# expender.net
KiCad netlist of a schematic drawn in EAGLE
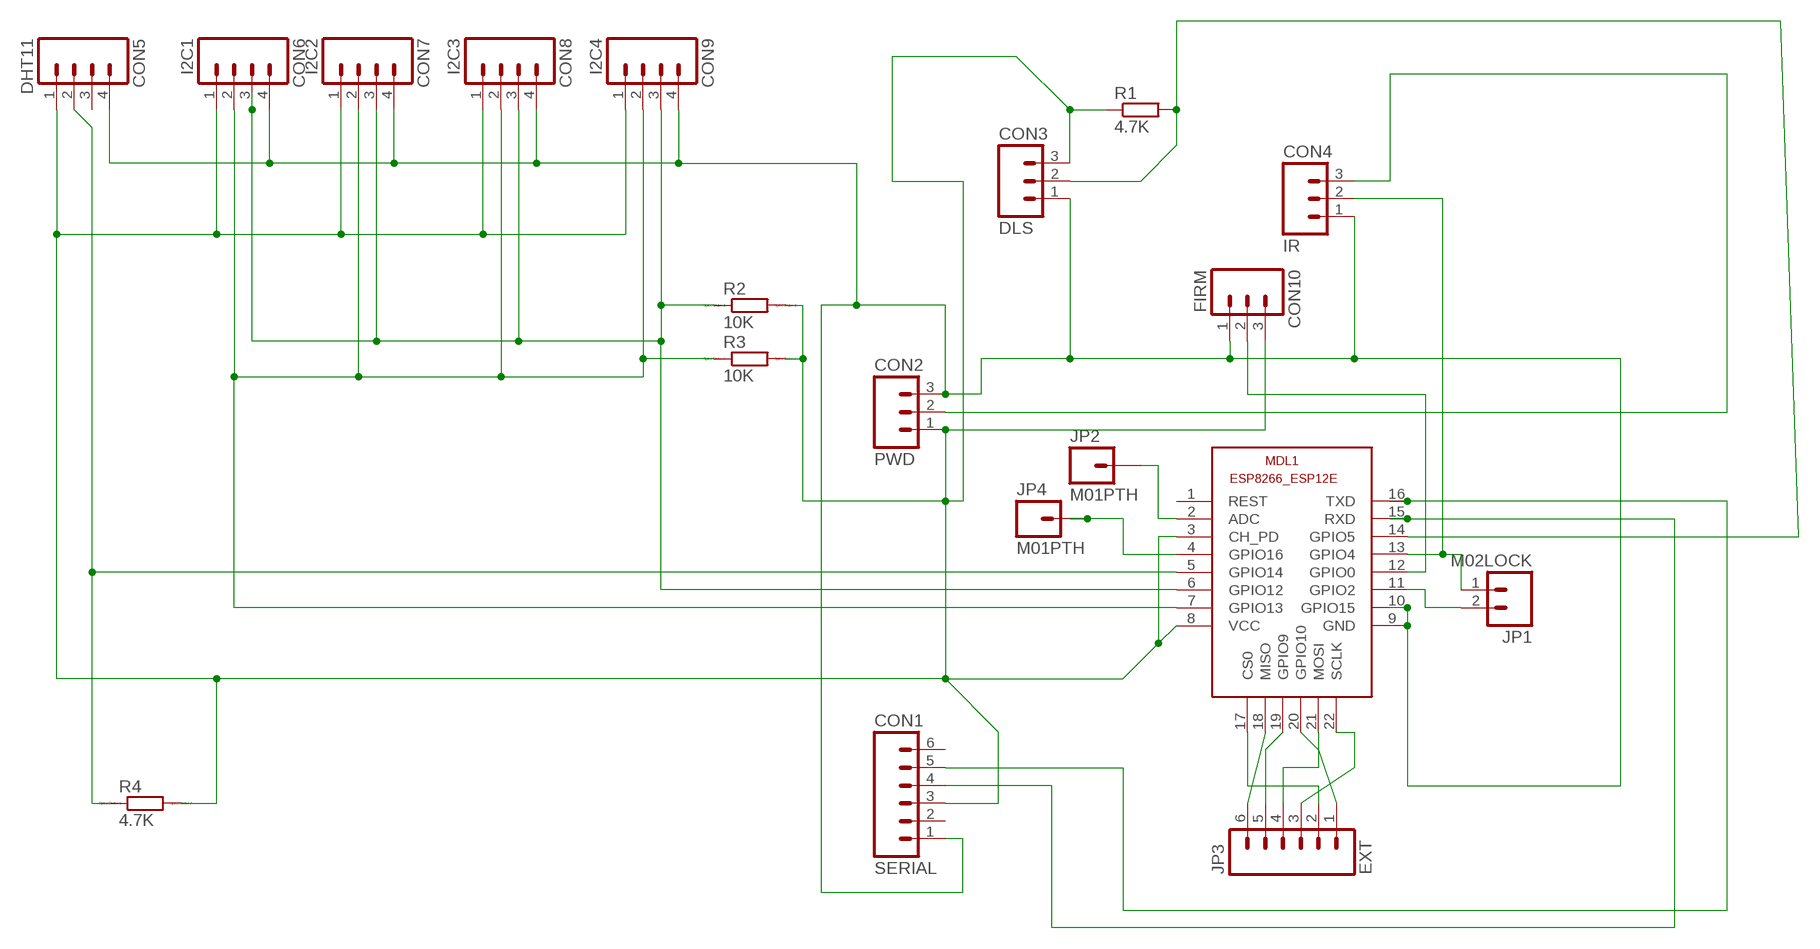
[diagram p0: schematic, sheet 1]

(export (version "E")
  (design (tool "Eeschema 10.0.6"))
  (components
    (comp (ref "CON1")
      (value "SERIAL")
      (footprint "eagle-import:1X06_LOCK")
      (libsource (lib "eagle-import") (part "M06LOCK"))
    )
    (comp (ref "CON2")
      (value "PWD")
      (footprint "eagle-import:1X03_LOCK")
      (libsource (lib "eagle-import") (part "M03LOCK"))
    )
    (comp (ref "CON3")
      (value "DLS")
      (footprint "eagle-import:1X03_LOCK")
      (libsource (lib "eagle-import") (part "M03LOCK"))
    )
    (comp (ref "CON4")
      (value "IR")
      (footprint "eagle-import:1X03_LOCK")
      (libsource (lib "eagle-import") (part "M03LOCK"))
    )
    (comp (ref "CON5")
      (value "DHT11")
      (footprint "eagle-import:1X04_LOCK")
      (libsource (lib "eagle-import") (part "M04LOCK"))
    )
    (comp (ref "CON6")
      (value "I2C1")
      (footprint "eagle-import:1X04_LOCK")
      (libsource (lib "eagle-import") (part "M04LOCK"))
    )
    (comp (ref "CON7")
      (value "I2C2")
      (footprint "eagle-import:1X04_LOCK")
      (libsource (lib "eagle-import") (part "M04LOCK"))
    )
    (comp (ref "CON8")
      (value "I2C3")
      (footprint "eagle-import:1X04_LOCK")
      (libsource (lib "eagle-import") (part "M04LOCK"))
    )
    (comp (ref "CON9")
      (value "I2C4")
      (footprint "eagle-import:1X04_LOCK")
      (libsource (lib "eagle-import") (part "M04LOCK"))
    )
    (comp (ref "CON10")
      (value "FIRM")
      (footprint "eagle-import:1X03_LOCK")
      (libsource (lib "eagle-import") (part "M03LOCK"))
    )
    (comp (ref "JP1")
      (value "M02LOCK")
      (footprint "eagle-import:1X02_LOCK")
      (libsource (lib "eagle-import") (part "M02LOCK"))
    )
    (comp (ref "JP2")
      (value "M01PTH")
      (footprint "eagle-import:1X01")
      (libsource (lib "eagle-import") (part "M01PTH"))
    )
    (comp (ref "JP3")
      (value "EXT")
      (footprint "eagle-import:1X06_LOCK")
      (libsource (lib "eagle-import") (part "M06LOCK"))
    )
    (comp (ref "JP4")
      (value "M01PTH")
      (footprint "eagle-import:1X01")
      (libsource (lib "eagle-import") (part "M01PTH"))
    )
    (comp (ref "MDL1")
      (value "ESP12E")
      (footprint "eagle-import:ESP8266-ESP12E")
      (libsource (lib "eagle-import") (part "ESP8266-12EESP8266-ESP12E"))
    )
    (comp (ref "R1")
      (value "4.7K")
      (footprint "eagle-import:0207_10")
      (libsource (lib "eagle-import") (part "R-EU_0207/10"))
    )
    (comp (ref "R2")
      (value "10K")
      (footprint "eagle-import:0207_10")
      (libsource (lib "eagle-import") (part "R0207/10"))
    )
    (comp (ref "R3")
      (value "10K")
      (footprint "eagle-import:0207_10")
      (libsource (lib "eagle-import") (part "R0207/10"))
    )
    (comp (ref "R4")
      (value "4.7K")
      (footprint "eagle-import:R1206")
      (libsource (lib "eagle-import") (part "RR1206"))
    )
  )
  (nets
    (net (code "1") (name "Net-(CON2-Pad2)") (class "Default")
      (node (ref "CON2") (pin "2") (pinfunction "2_2") (pintype "passive"))
      (node (ref "CON4") (pin "3") (pinfunction "3_3") (pintype "passive"))
    )
    (net (code "2") (name "Net-(MDL1-ADC)") (class "Default")
      (node (ref "JP2") (pin "1") (pinfunction "1_1") (pintype "passive"))
      (node (ref "MDL1") (pin "2") (pinfunction "ADC_2") (pintype "bidirectional"))
    )
    (net (code "3") (name "Net-(MDL1-CH_PD)") (class "Default")
      (node (ref "CON1") (pin "3") (pinfunction "3_3") (pintype "passive"))
      (node (ref "CON10") (pin "3") (pinfunction "3_3") (pintype "passive"))
      (node (ref "CON2") (pin "1") (pinfunction "1_1") (pintype "passive"))
      (node (ref "CON3") (pin "3") (pinfunction "3_3") (pintype "passive"))
      (node (ref "CON5") (pin "1") (pinfunction "1_1") (pintype "passive"))
      (node (ref "CON6") (pin "1") (pinfunction "1_1") (pintype "passive"))
      (node (ref "CON7") (pin "1") (pinfunction "1_1") (pintype "passive"))
      (node (ref "CON8") (pin "1") (pinfunction "1_1") (pintype "passive"))
      (node (ref "CON9") (pin "1") (pinfunction "1_1") (pintype "passive"))
      (node (ref "MDL1") (pin "3") (pinfunction "CH_PD_3") (pintype "bidirectional"))
      (node (ref "MDL1") (pin "8") (pinfunction "VCC_8") (pintype "bidirectional"))
      (node (ref "R1") (pin "1") (pinfunction "1_1") (pintype "passive"))
      (node (ref "R2") (pin "2") (pinfunction "2_2") (pintype "passive"))
      (node (ref "R3") (pin "2") (pinfunction "2_2") (pintype "passive"))
      (node (ref "R4") (pin "2") (pinfunction "2_2") (pintype "passive"))
    )
    (net (code "4") (name "Net-(MDL1-CS0)") (class "Default")
      (node (ref "JP3") (pin "2") (pinfunction "2_2") (pintype "passive"))
      (node (ref "MDL1") (pin "17") (pinfunction "CS0_17") (pintype "bidirectional"))
    )
    (net (code "5") (name "Net-(MDL1-GND)") (class "Default")
      (node (ref "CON1") (pin "1") (pinfunction "1_1") (pintype "passive"))
      (node (ref "CON10") (pin "1") (pinfunction "1_1") (pintype "passive"))
      (node (ref "CON2") (pin "3") (pinfunction "3_3") (pintype "passive"))
      (node (ref "CON3") (pin "1") (pinfunction "1_1") (pintype "passive"))
      (node (ref "CON4") (pin "1") (pinfunction "1_1") (pintype "passive"))
      (node (ref "CON5") (pin "4") (pinfunction "4_4") (pintype "passive"))
      (node (ref "CON6") (pin "4") (pinfunction "4_4") (pintype "passive"))
      (node (ref "CON7") (pin "4") (pinfunction "4_4") (pintype "passive"))
      (node (ref "CON8") (pin "4") (pinfunction "4_4") (pintype "passive"))
      (node (ref "CON9") (pin "4") (pinfunction "4_4") (pintype "passive"))
      (node (ref "MDL1") (pin "10") (pinfunction "GPIO15_10") (pintype "bidirectional"))
      (node (ref "MDL1") (pin "9") (pinfunction "GND_9") (pintype "bidirectional"))
    )
    (net (code "6") (name "Net-(MDL1-GPIO0)") (class "Default")
      (node (ref "CON10") (pin "2") (pinfunction "2_2") (pintype "passive"))
      (node (ref "MDL1") (pin "12") (pinfunction "GPIO0_12") (pintype "bidirectional"))
    )
    (net (code "7") (name "Net-(MDL1-GPIO2)") (class "Default")
      (node (ref "JP1") (pin "2") (pinfunction "2_2") (pintype "passive"))
      (node (ref "MDL1") (pin "11") (pinfunction "GPIO2_11") (pintype "bidirectional"))
    )
    (net (code "8") (name "Net-(MDL1-GPIO4)") (class "Default")
      (node (ref "CON4") (pin "2") (pinfunction "2_2") (pintype "passive"))
      (node (ref "JP1") (pin "1") (pinfunction "1_1") (pintype "passive"))
      (node (ref "MDL1") (pin "13") (pinfunction "GPIO4_13") (pintype "bidirectional"))
    )
    (net (code "9") (name "Net-(MDL1-GPIO5)") (class "Default")
      (node (ref "CON3") (pin "2") (pinfunction "2_2") (pintype "passive"))
      (node (ref "MDL1") (pin "14") (pinfunction "GPIO5_14") (pintype "bidirectional"))
      (node (ref "R1") (pin "2") (pinfunction "2_2") (pintype "passive"))
    )
    (net (code "10") (name "Net-(MDL1-GPIO9)") (class "Default")
      (node (ref "JP3") (pin "5") (pinfunction "5_5") (pintype "passive"))
      (node (ref "MDL1") (pin "19") (pinfunction "GPIO9_19") (pintype "bidirectional"))
    )
    (net (code "11") (name "Net-(MDL1-GPIO10)") (class "Default")
      (node (ref "JP3") (pin "1") (pinfunction "1_1") (pintype "passive"))
      (node (ref "MDL1") (pin "20") (pinfunction "GPIO10_20") (pintype "bidirectional"))
    )
    (net (code "12") (name "Net-(MDL1-GPIO12)") (class "Default")
      (node (ref "CON6") (pin "3") (pinfunction "3_3") (pintype "passive"))
      (node (ref "CON7") (pin "3") (pinfunction "3_3") (pintype "passive"))
      (node (ref "CON8") (pin "3") (pinfunction "3_3") (pintype "passive"))
      (node (ref "CON9") (pin "3") (pinfunction "3_3") (pintype "passive"))
      (node (ref "MDL1") (pin "6") (pinfunction "GPIO12_6") (pintype "bidirectional"))
      (node (ref "R2") (pin "1") (pinfunction "1_1") (pintype "passive"))
    )
    (net (code "13") (name "Net-(MDL1-GPIO13)") (class "Default")
      (node (ref "CON6") (pin "2") (pinfunction "2_2") (pintype "passive"))
      (node (ref "CON7") (pin "2") (pinfunction "2_2") (pintype "passive"))
      (node (ref "CON8") (pin "2") (pinfunction "2_2") (pintype "passive"))
      (node (ref "CON9") (pin "2") (pinfunction "2_2") (pintype "passive"))
      (node (ref "MDL1") (pin "7") (pinfunction "GPIO13_7") (pintype "bidirectional"))
      (node (ref "R3") (pin "1") (pinfunction "1_1") (pintype "passive"))
    )
    (net (code "14") (name "Net-(MDL1-GPIO14)") (class "Default")
      (node (ref "CON5") (pin "2") (pinfunction "2_2") (pintype "passive"))
      (node (ref "MDL1") (pin "5") (pinfunction "GPIO14_5") (pintype "bidirectional"))
      (node (ref "R4") (pin "1") (pinfunction "1_1") (pintype "passive"))
    )
    (net (code "15") (name "Net-(MDL1-GPIO16)") (class "Default")
      (node (ref "JP4") (pin "1") (pinfunction "1_1") (pintype "passive"))
      (node (ref "MDL1") (pin "4") (pinfunction "GPIO16_4") (pintype "bidirectional"))
    )
    (net (code "16") (name "Net-(MDL1-MISO)") (class "Default")
      (node (ref "JP3") (pin "6") (pinfunction "6_6") (pintype "passive"))
      (node (ref "MDL1") (pin "18") (pinfunction "MISO_18") (pintype "bidirectional"))
    )
    (net (code "17") (name "Net-(MDL1-MOSI)") (class "Default")
      (node (ref "JP3") (pin "4") (pinfunction "4_4") (pintype "passive"))
      (node (ref "MDL1") (pin "21") (pinfunction "MOSI_21") (pintype "bidirectional"))
    )
    (net (code "18") (name "Net-(MDL1-RXD)") (class "Default")
      (node (ref "CON1") (pin "4") (pinfunction "4_4") (pintype "passive"))
      (node (ref "MDL1") (pin "15") (pinfunction "RXD_15") (pintype "bidirectional"))
    )
    (net (code "19") (name "Net-(MDL1-SCLK)") (class "Default")
      (node (ref "JP3") (pin "3") (pinfunction "3_3") (pintype "passive"))
      (node (ref "MDL1") (pin "22") (pinfunction "SCLK_22") (pintype "bidirectional"))
    )
    (net (code "20") (name "Net-(MDL1-TXD)") (class "Default")
      (node (ref "CON1") (pin "5") (pinfunction "5_5") (pintype "passive"))
      (node (ref "MDL1") (pin "16") (pinfunction "TXD_16") (pintype "bidirectional"))
    )
    (net (code "21") (name "unconnected-(CON1-Pad2)") (class "Default")
      (node (ref "CON1") (pin "2") (pinfunction "2_2") (pintype "passive"))
    )
    (net (code "22") (name "unconnected-(CON1-Pad6)") (class "Default")
      (node (ref "CON1") (pin "6") (pinfunction "6_6") (pintype "passive"))
    )
    (net (code "23") (name "unconnected-(CON5-Pad3)") (class "Default")
      (node (ref "CON5") (pin "3") (pinfunction "3_3") (pintype "passive"))
    )
    (net (code "24") (name "unconnected-(MDL1-REST-Pad1)") (class "Default")
      (node (ref "MDL1") (pin "1") (pinfunction "REST_1") (pintype "bidirectional"))
    )
  )
)
